# mod_main.net
KiCad netlist of a schematic drawn in EAGLE
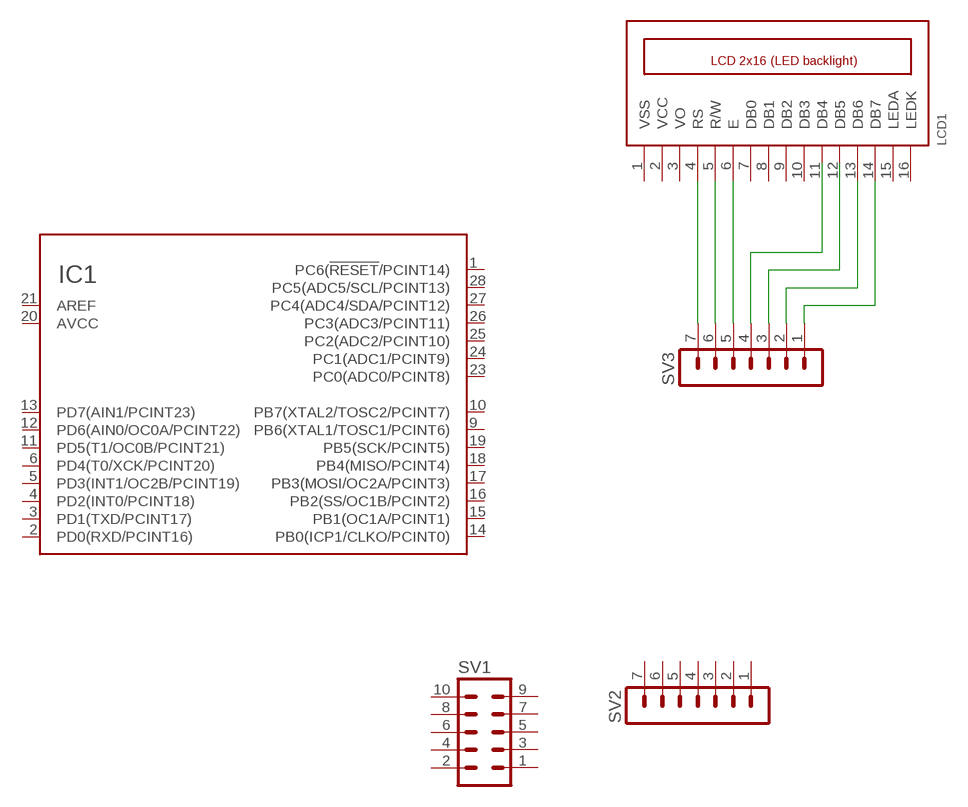
[diagram p0: schematic, sheet 1]

(export (version "E")
  (design (tool "Eeschema 10.0.6"))
  (components
    (comp (ref "IC1")
      (value "ATMEGA48/88/168/328-PU(DIP28)PU")
      (footprint "eagle-import:DIL28")
      (libsource (lib "eagle-import") (part "ATMEGA48/88/168/328-PU(DIP28)PU"))
    )
    (comp (ref "LCD1")
      (value "LCD_2X16_SIL")
      (footprint "eagle-import:HY-1602F")
      (libsource (lib "eagle-import") (part "LCD_2X16_SIL"))
    )
    (comp (ref "SV1")
      (value "MA05-2")
      (footprint "eagle-import:MA05-2")
      (libsource (lib "eagle-import") (part "MA05-2"))
    )
    (comp (ref "SV2")
      (value "MA07-1")
      (footprint "eagle-import:MA07-1")
      (libsource (lib "eagle-import") (part "MA07-1"))
    )
    (comp (ref "SV3")
      (value "MA07-1")
      (footprint "eagle-import:MA07-1")
      (libsource (lib "eagle-import") (part "MA07-1"))
    )
  )
  (nets
    (net (code "1") (name "/AVCC") (class "Default")
      (node (ref "IC1") (pin "20") (pinfunction "AVCC_20") (pintype "power_in"))
    )
    (net (code "2") (name "/VCC") (class "Default")
      (node (ref "LCD1") (pin "2") (pinfunction "VCC_2") (pintype "power_in"))
    )
    (net (code "3") (name "/VSS") (class "Default")
      (node (ref "LCD1") (pin "1") (pinfunction "VSS_1") (pintype "power_in"))
    )
    (net (code "4") (name "Net-(LCD1-DB6)") (class "Default")
      (node (ref "LCD1") (pin "13") (pinfunction "DB6_13") (pintype "bidirectional"))
      (node (ref "SV3") (pin "2") (pinfunction "2_2") (pintype "passive"))
    )
    (net (code "5") (name "Net-(LCD1-DB7)") (class "Default")
      (node (ref "LCD1") (pin "14") (pinfunction "DB7_14") (pintype "bidirectional"))
      (node (ref "SV3") (pin "1") (pinfunction "1_1") (pintype "passive"))
    )
    (net (code "6") (name "Net-(LCD1-E)") (class "Default")
      (node (ref "LCD1") (pin "6") (pinfunction "E_6") (pintype "input"))
      (node (ref "SV3") (pin "5") (pinfunction "5_5") (pintype "passive"))
    )
    (net (code "7") (name "Net-(LCD1-RS)") (class "Default")
      (node (ref "LCD1") (pin "4") (pinfunction "RS_4") (pintype "input"))
      (node (ref "SV3") (pin "7") (pinfunction "7_7") (pintype "passive"))
    )
    (net (code "8") (name "Net-(LCD1-R{slash}W)") (class "Default")
      (node (ref "LCD1") (pin "5") (pinfunction "R/W_5") (pintype "input"))
      (node (ref "SV3") (pin "6") (pinfunction "6_6") (pintype "passive"))
    )
    (net (code "9") (name "unconnected-(IC1A-AREF-Pad21)") (class "Default")
      (node (ref "IC1") (pin "21") (pinfunction "AREF_21") (pintype "passive"))
    )
    (net (code "10") (name "unconnected-(IC1A-PB0(ICP1{slash}CLKO{slash}PCINT0)-Pad14)") (class "Default")
      (node (ref "IC1") (pin "14") (pinfunction "PB0(ICP1/CLKO/PCINT0)_14") (pintype "bidirectional"))
    )
    (net (code "11") (name "unconnected-(IC1A-PB1(OC1A{slash}PCINT1)-Pad15)") (class "Default")
      (node (ref "IC1") (pin "15") (pinfunction "PB1(OC1A/PCINT1)_15") (pintype "bidirectional"))
    )
    (net (code "12") (name "unconnected-(IC1A-PB2(SS{slash}OC1B{slash}PCINT2)-Pad16)") (class "Default")
      (node (ref "IC1") (pin "16") (pinfunction "PB2(SS/OC1B/PCINT2)_16") (pintype "bidirectional"))
    )
    (net (code "13") (name "unconnected-(IC1A-PB3(MOSI{slash}OC2A{slash}PCINT3)-Pad17)") (class "Default")
      (node (ref "IC1") (pin "17") (pinfunction "PB3(MOSI/OC2A/PCINT3)_17") (pintype "bidirectional"))
    )
    (net (code "14") (name "unconnected-(IC1A-PB4(MISO{slash}PCINT4)-Pad18)") (class "Default")
      (node (ref "IC1") (pin "18") (pinfunction "PB4(MISO/PCINT4)_18") (pintype "bidirectional"))
    )
    (net (code "15") (name "unconnected-(IC1A-PB5(SCK{slash}PCINT5)-Pad19)") (class "Default")
      (node (ref "IC1") (pin "19") (pinfunction "PB5(SCK/PCINT5)_19") (pintype "bidirectional"))
    )
    (net (code "16") (name "unconnected-(IC1A-PB6(XTAL1{slash}TOSC1{slash}PCINT6)-Pad9)") (class "Default")
      (node (ref "IC1") (pin "9") (pinfunction "PB6(XTAL1/TOSC1/PCINT6)_9") (pintype "bidirectional"))
    )
    (net (code "17") (name "unconnected-(IC1A-PB7(XTAL2{slash}TOSC2{slash}PCINT7)-Pad10)") (class "Default")
      (node (ref "IC1") (pin "10") (pinfunction "PB7(XTAL2/TOSC2/PCINT7)_10") (pintype "bidirectional"))
    )
    (net (code "18") (name "unconnected-(IC1A-PC0(ADC0{slash}PCINT8)-Pad23)") (class "Default")
      (node (ref "IC1") (pin "23") (pinfunction "PC0(ADC0/PCINT8)_23") (pintype "bidirectional"))
    )
    (net (code "19") (name "unconnected-(IC1A-PC1(ADC1{slash}PCINT9)-Pad24)") (class "Default")
      (node (ref "IC1") (pin "24") (pinfunction "PC1(ADC1/PCINT9)_24") (pintype "bidirectional"))
    )
    (net (code "20") (name "unconnected-(IC1A-PC2(ADC2{slash}PCINT10)-Pad25)") (class "Default")
      (node (ref "IC1") (pin "25") (pinfunction "PC2(ADC2/PCINT10)_25") (pintype "bidirectional"))
    )
    (net (code "21") (name "unconnected-(IC1A-PC3(ADC3{slash}PCINT11)-Pad26)") (class "Default")
      (node (ref "IC1") (pin "26") (pinfunction "PC3(ADC3/PCINT11)_26") (pintype "bidirectional"))
    )
    (net (code "22") (name "unconnected-(IC1A-PC4(ADC4{slash}SDA{slash}PCINT12)-Pad27)") (class "Default")
      (node (ref "IC1") (pin "27") (pinfunction "PC4(ADC4/SDA/PCINT12)_27") (pintype "bidirectional"))
    )
    (net (code "23") (name "unconnected-(IC1A-PC5(ADC5{slash}SCL{slash}PCINT13)-Pad28)") (class "Default")
      (node (ref "IC1") (pin "28") (pinfunction "PC5(ADC5/SCL/PCINT13)_28") (pintype "bidirectional"))
    )
    (net (code "24") (name "unconnected-(IC1A-PC6(~{RESET}{slash}PCINT14)-Pad1)") (class "Default")
      (node (ref "IC1") (pin "1") (pinfunction "PC6(~{RESET}/PCINT14)_1") (pintype "bidirectional"))
    )
    (net (code "25") (name "unconnected-(IC1A-PD0(RXD{slash}PCINT16)-Pad2)") (class "Default")
      (node (ref "IC1") (pin "2") (pinfunction "PD0(RXD/PCINT16)_2") (pintype "bidirectional"))
    )
    (net (code "26") (name "unconnected-(IC1A-PD1(TXD{slash}PCINT17)-Pad3)") (class "Default")
      (node (ref "IC1") (pin "3") (pinfunction "PD1(TXD/PCINT17)_3") (pintype "bidirectional"))
    )
    (net (code "27") (name "unconnected-(IC1A-PD2(INT0{slash}PCINT18)-Pad4)") (class "Default")
      (node (ref "IC1") (pin "4") (pinfunction "PD2(INT0/PCINT18)_4") (pintype "bidirectional"))
    )
    (net (code "28") (name "unconnected-(IC1A-PD3(INT1{slash}OC2B{slash}PCINT19)-Pad5)") (class "Default")
      (node (ref "IC1") (pin "5") (pinfunction "PD3(INT1/OC2B/PCINT19)_5") (pintype "bidirectional"))
    )
    (net (code "29") (name "unconnected-(IC1A-PD4(T0{slash}XCK{slash}PCINT20)-Pad6)") (class "Default")
      (node (ref "IC1") (pin "6") (pinfunction "PD4(T0/XCK/PCINT20)_6") (pintype "bidirectional"))
    )
    (net (code "30") (name "unconnected-(IC1A-PD5(T1{slash}OC0B{slash}PCINT21)-Pad11)") (class "Default")
      (node (ref "IC1") (pin "11") (pinfunction "PD5(T1/OC0B/PCINT21)_11") (pintype "bidirectional"))
    )
    (net (code "31") (name "unconnected-(IC1A-PD6(AIN0{slash}OC0A{slash}PCINT22)-Pad12)") (class "Default")
      (node (ref "IC1") (pin "12") (pinfunction "PD6(AIN0/OC0A/PCINT22)_12") (pintype "bidirectional"))
    )
    (net (code "32") (name "unconnected-(IC1A-PD7(AIN1{slash}PCINT23)-Pad13)") (class "Default")
      (node (ref "IC1") (pin "13") (pinfunction "PD7(AIN1/PCINT23)_13") (pintype "bidirectional"))
    )
    (net (code "33") (name "unconnected-(LCD1-DB0-Pad7)") (class "Default")
      (node (ref "LCD1") (pin "7") (pinfunction "DB0_7") (pintype "bidirectional"))
    )
    (net (code "34") (name "unconnected-(LCD1-DB1-Pad8)") (class "Default")
      (node (ref "LCD1") (pin "8") (pinfunction "DB1_8") (pintype "bidirectional"))
    )
    (net (code "35") (name "unconnected-(LCD1-DB2-Pad9)") (class "Default")
      (node (ref "LCD1") (pin "9") (pinfunction "DB2_9") (pintype "bidirectional"))
    )
    (net (code "36") (name "unconnected-(LCD1-DB3-Pad10)") (class "Default")
      (node (ref "LCD1") (pin "10") (pinfunction "DB3_10") (pintype "bidirectional"))
    )
    (net (code "37") (name "unconnected-(LCD1-DB4-Pad11)") (class "Default")
      (node (ref "LCD1") (pin "11") (pinfunction "DB4_11") (pintype "bidirectional"))
    )
    (net (code "38") (name "unconnected-(LCD1-DB5-Pad12)") (class "Default")
      (node (ref "LCD1") (pin "12") (pinfunction "DB5_12") (pintype "bidirectional"))
    )
    (net (code "39") (name "unconnected-(LCD1-LEDA-Pad15)") (class "Default")
      (node (ref "LCD1") (pin "15") (pinfunction "LEDA_15") (pintype "passive"))
    )
    (net (code "40") (name "unconnected-(LCD1-LEDK-Pad16)") (class "Default")
      (node (ref "LCD1") (pin "16") (pinfunction "LEDK_16") (pintype "passive"))
    )
    (net (code "41") (name "unconnected-(LCD1-VO-Pad3)") (class "Default")
      (node (ref "LCD1") (pin "3") (pinfunction "VO_3") (pintype "input"))
    )
    (net (code "42") (name "unconnected-(SV1-Pad1)") (class "Default")
      (node (ref "SV1") (pin "1") (pinfunction "1_1") (pintype "passive"))
    )
    (net (code "43") (name "unconnected-(SV1-Pad2)") (class "Default")
      (node (ref "SV1") (pin "2") (pinfunction "2_2") (pintype "passive"))
    )
    (net (code "44") (name "unconnected-(SV1-Pad3)") (class "Default")
      (node (ref "SV1") (pin "3") (pinfunction "3_3") (pintype "passive"))
    )
    (net (code "45") (name "unconnected-(SV1-Pad4)") (class "Default")
      (node (ref "SV1") (pin "4") (pinfunction "4_4") (pintype "passive"))
    )
    (net (code "46") (name "unconnected-(SV1-Pad5)") (class "Default")
      (node (ref "SV1") (pin "5") (pinfunction "5_5") (pintype "passive"))
    )
    (net (code "47") (name "unconnected-(SV1-Pad6)") (class "Default")
      (node (ref "SV1") (pin "6") (pinfunction "6_6") (pintype "passive"))
    )
    (net (code "48") (name "unconnected-(SV1-Pad7)") (class "Default")
      (node (ref "SV1") (pin "7") (pinfunction "7_7") (pintype "passive"))
    )
    (net (code "49") (name "unconnected-(SV1-Pad8)") (class "Default")
      (node (ref "SV1") (pin "8") (pinfunction "8_8") (pintype "passive"))
    )
    (net (code "50") (name "unconnected-(SV1-Pad9)") (class "Default")
      (node (ref "SV1") (pin "9") (pinfunction "9_9") (pintype "passive"))
    )
    (net (code "51") (name "unconnected-(SV1-Pad10)") (class "Default")
      (node (ref "SV1") (pin "10") (pinfunction "10_10") (pintype "passive"))
    )
    (net (code "52") (name "unconnected-(SV2-Pad1)") (class "Default")
      (node (ref "SV2") (pin "1") (pinfunction "1_1") (pintype "passive"))
    )
    (net (code "53") (name "unconnected-(SV2-Pad2)") (class "Default")
      (node (ref "SV2") (pin "2") (pinfunction "2_2") (pintype "passive"))
    )
    (net (code "54") (name "unconnected-(SV2-Pad3)") (class "Default")
      (node (ref "SV2") (pin "3") (pinfunction "3_3") (pintype "passive"))
    )
    (net (code "55") (name "unconnected-(SV2-Pad4)") (class "Default")
      (node (ref "SV2") (pin "4") (pinfunction "4_4") (pintype "passive"))
    )
    (net (code "56") (name "unconnected-(SV2-Pad5)") (class "Default")
      (node (ref "SV2") (pin "5") (pinfunction "5_5") (pintype "passive"))
    )
    (net (code "57") (name "unconnected-(SV2-Pad6)") (class "Default")
      (node (ref "SV2") (pin "6") (pinfunction "6_6") (pintype "passive"))
    )
    (net (code "58") (name "unconnected-(SV2-Pad7)") (class "Default")
      (node (ref "SV2") (pin "7") (pinfunction "7_7") (pintype "passive"))
    )
    (net (code "59") (name "unconnected-(SV3-Pad3)") (class "Default")
      (node (ref "SV3") (pin "3") (pinfunction "3_3") (pintype "passive"))
    )
    (net (code "60") (name "unconnected-(SV3-Pad4)") (class "Default")
      (node (ref "SV3") (pin "4") (pinfunction "4_4") (pintype "passive"))
    )
  )
)
